# rev1.net
KiCad netlist of a schematic drawn in EAGLE
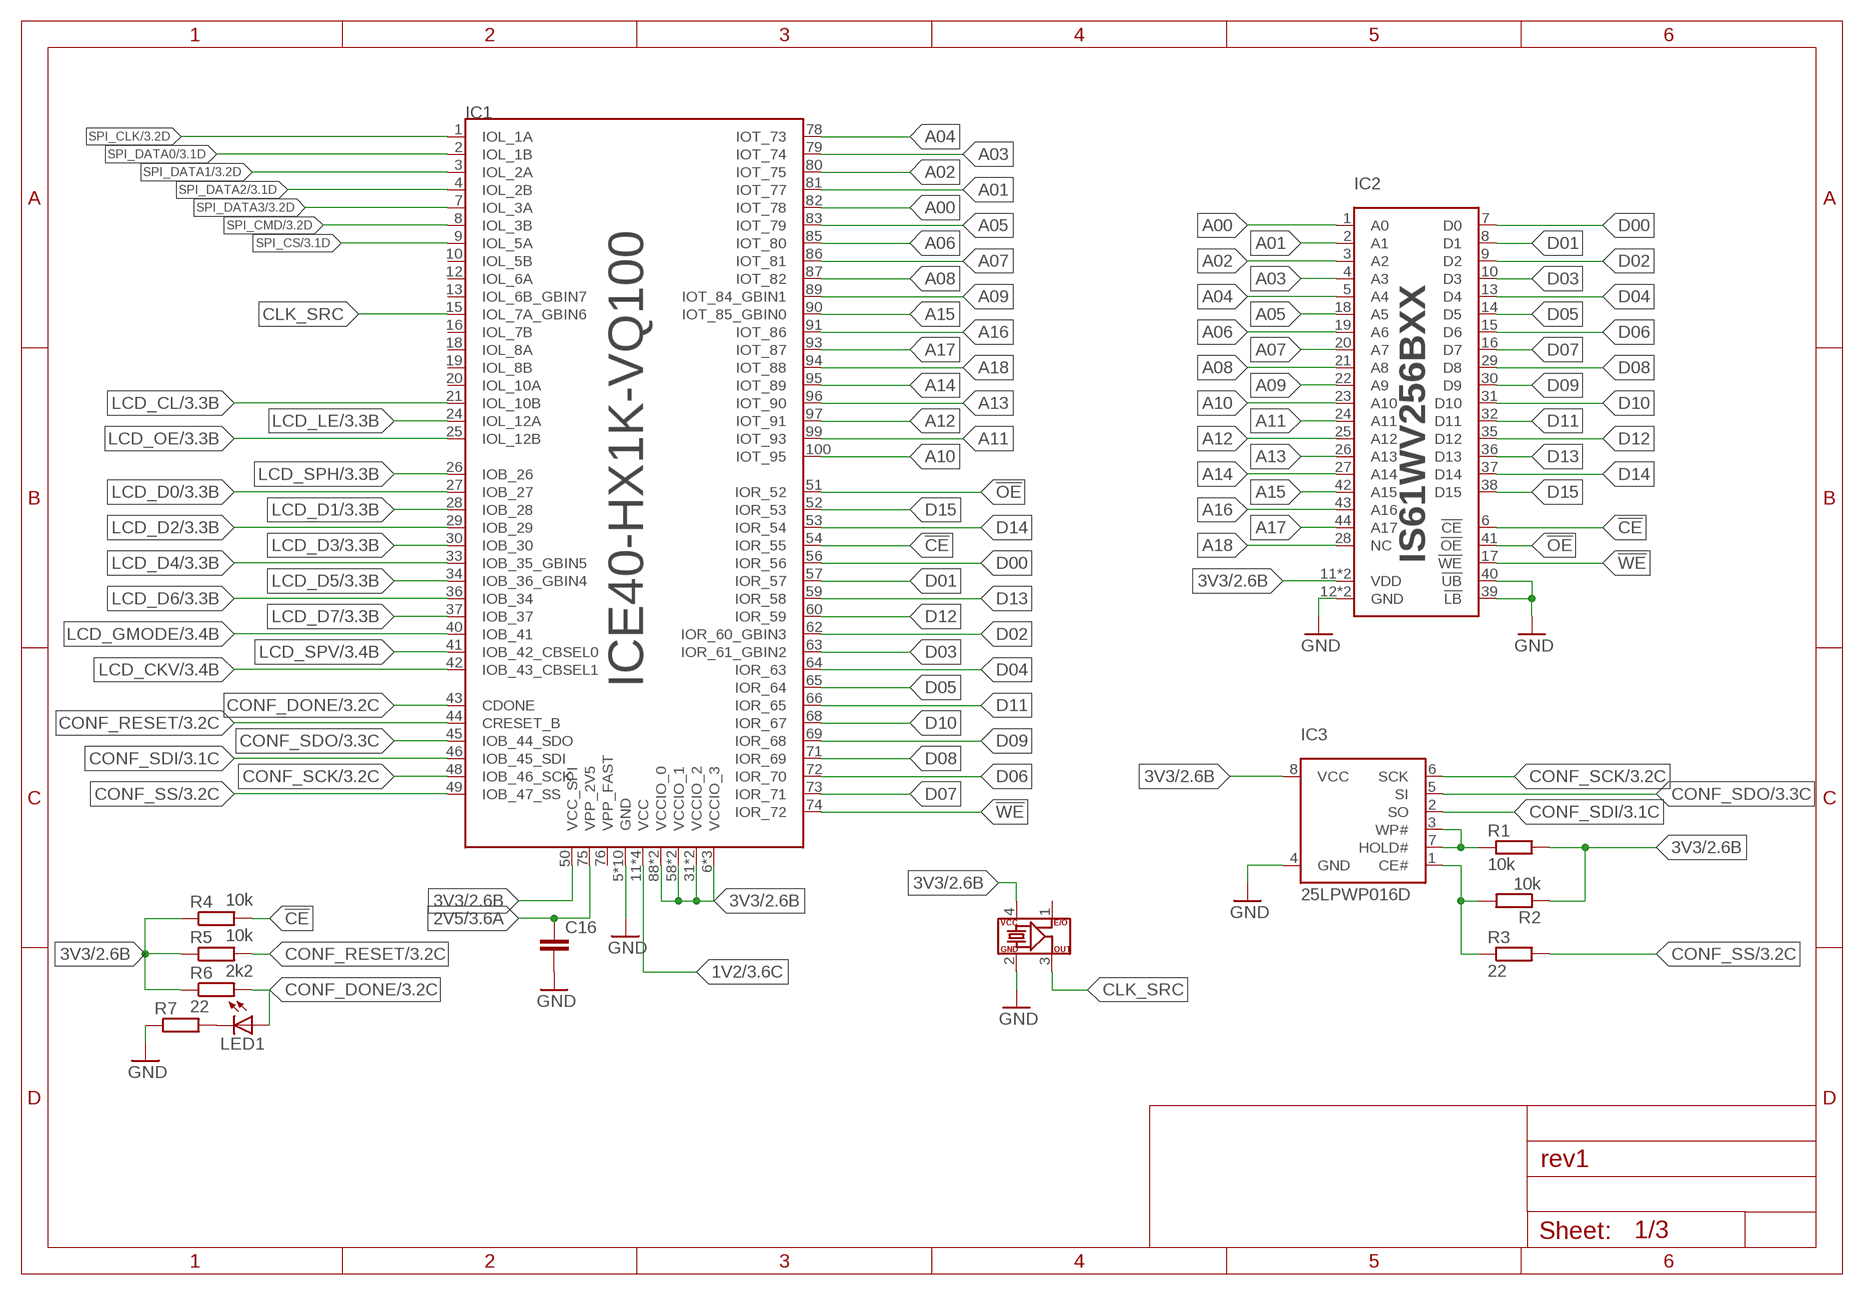
[diagram p0: schematic, sheet 1]
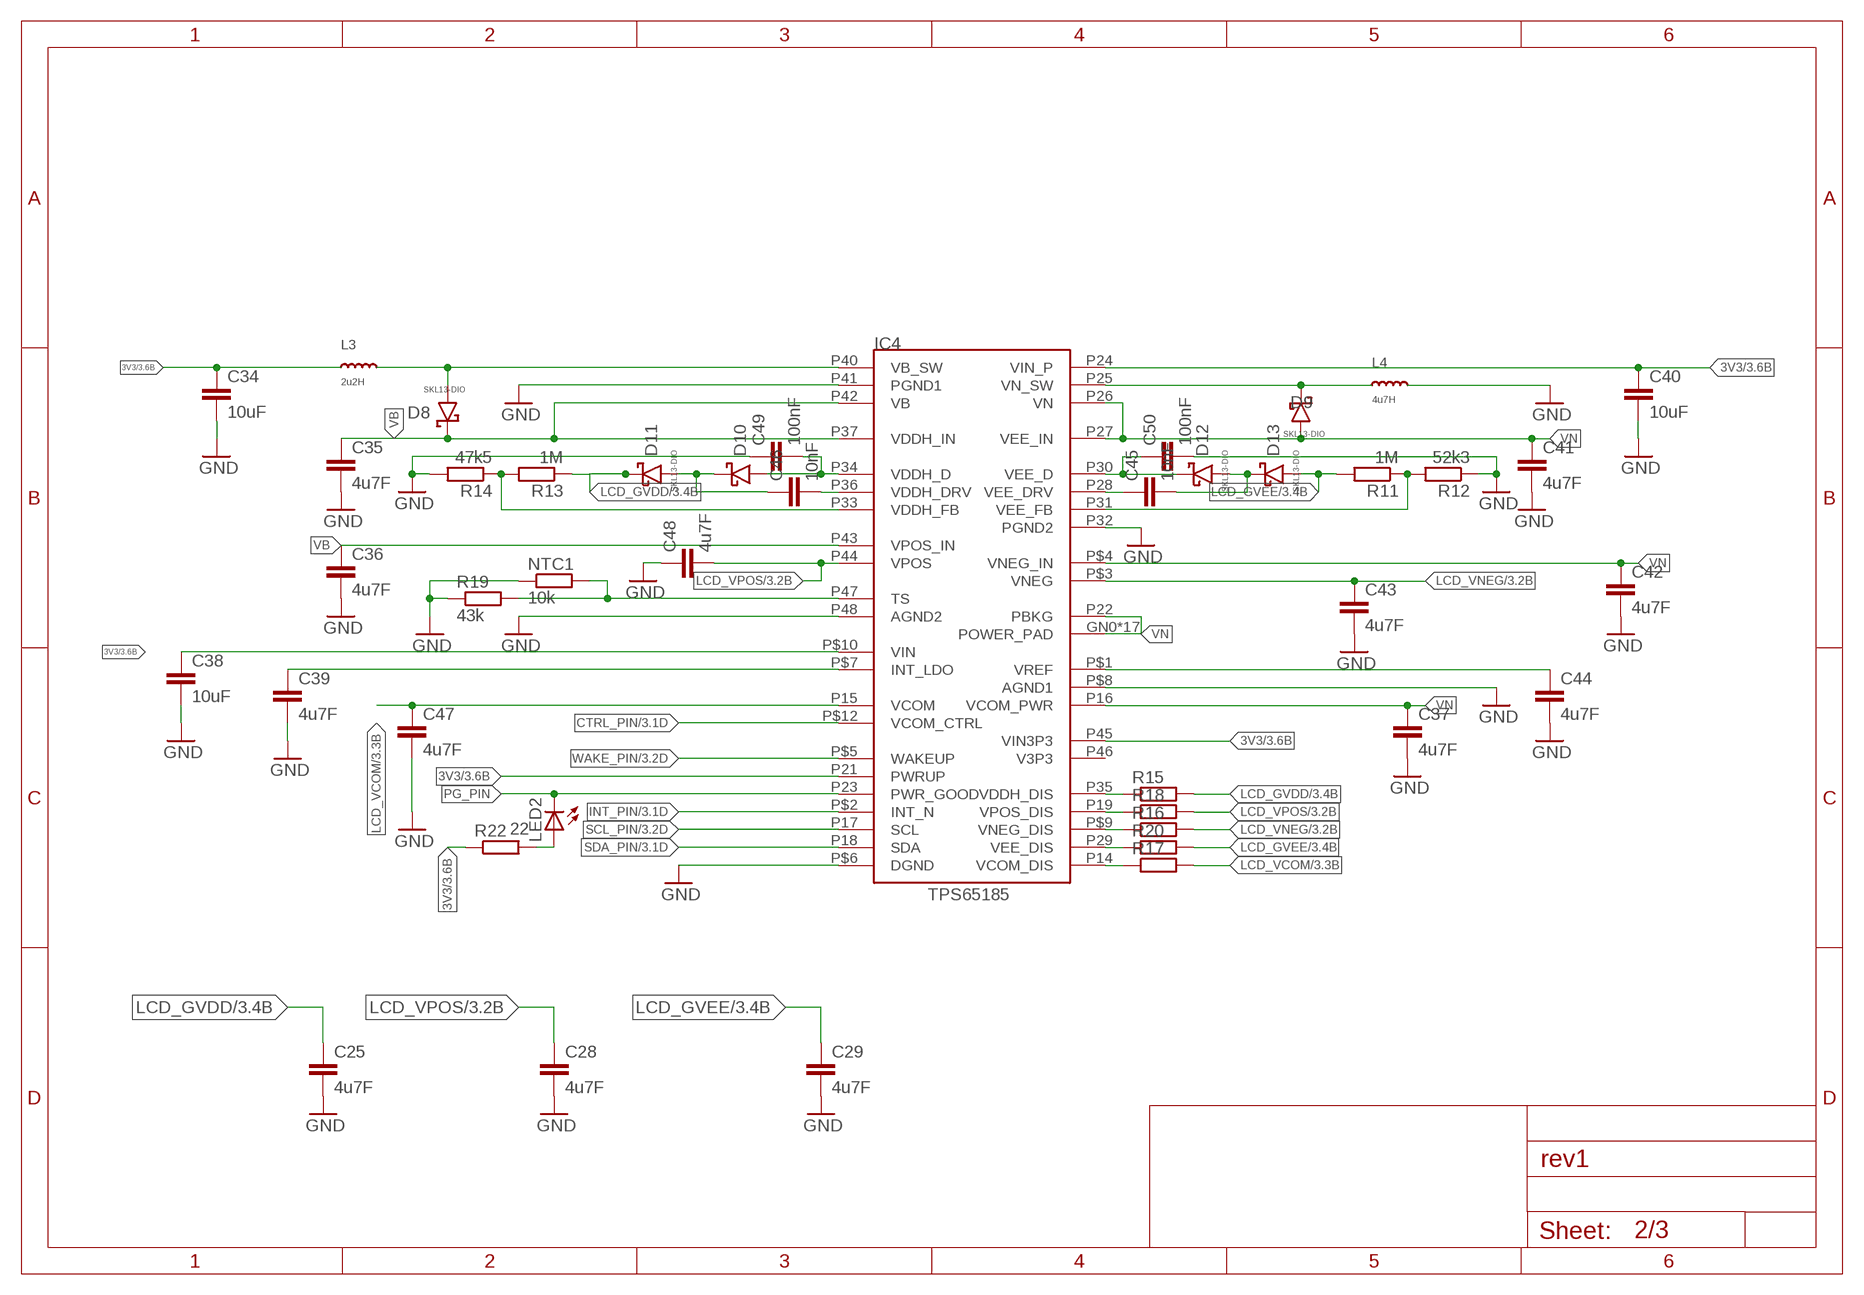
[diagram p1: schematic, sheet 2]
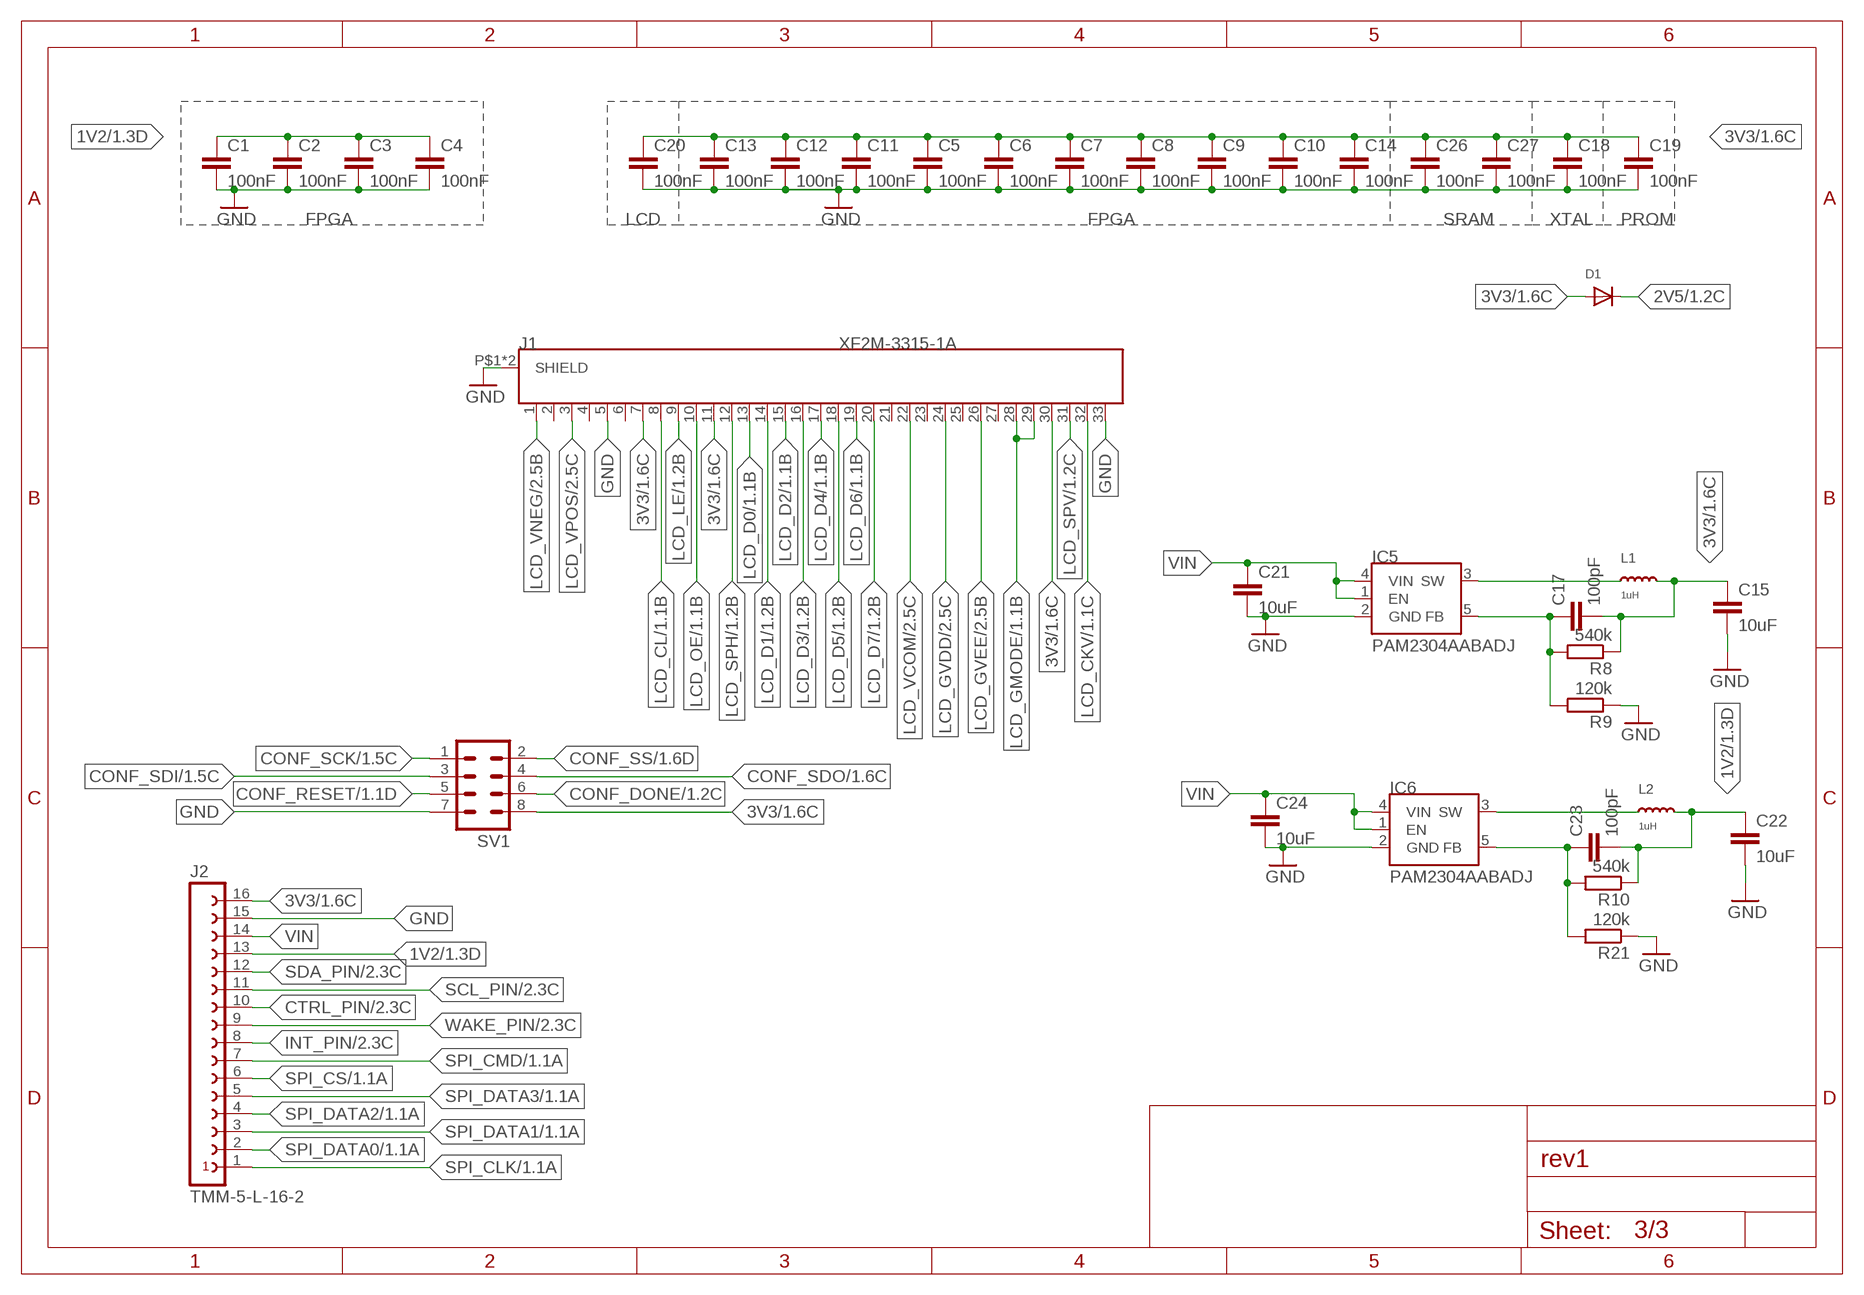
[diagram p2: schematic, sheet 3]

(export (version "E")
  (design (tool "Eeschema 10.0.6"))
  (components
    (comp (ref "C25")
      (value "4u7F")
      (footprint "eagle-import:C0805")
      (libsource (lib "eagle-import") (part "C-EUC0805"))
    )
    (comp (ref "C28")
      (value "4u7F")
      (footprint "eagle-import:C0805")
      (libsource (lib "eagle-import") (part "C-EUC0805"))
    )
    (comp (ref "C29")
      (value "4u7F")
      (footprint "eagle-import:C0805")
      (libsource (lib "eagle-import") (part "C-EUC0805"))
    )
    (comp (ref "C34")
      (value "10uF")
      (footprint "eagle-import:C0805")
      (libsource (lib "eagle-import") (part "C-EUC0805"))
    )
    (comp (ref "C35")
      (value "4u7F")
      (footprint "eagle-import:C0805")
      (libsource (lib "eagle-import") (part "C-EUC0805"))
    )
    (comp (ref "C36")
      (value "4u7F")
      (footprint "eagle-import:C0805")
      (libsource (lib "eagle-import") (part "C-EUC0805"))
    )
    (comp (ref "C37")
      (value "4u7F")
      (footprint "eagle-import:C0805")
      (libsource (lib "eagle-import") (part "C-EUC0805"))
    )
    (comp (ref "C38")
      (value "10uF")
      (footprint "eagle-import:C0805")
      (libsource (lib "eagle-import") (part "C-EUC0805"))
    )
    (comp (ref "C39")
      (value "4u7F")
      (footprint "eagle-import:C0603")
      (libsource (lib "eagle-import") (part "C-EUC0603"))
    )
    (comp (ref "C40")
      (value "10uF")
      (footprint "eagle-import:C0805")
      (libsource (lib "eagle-import") (part "C-EUC0805"))
    )
    (comp (ref "C41")
      (value "4u7F")
      (footprint "eagle-import:C0805")
      (libsource (lib "eagle-import") (part "C-EUC0805"))
    )
    (comp (ref "C42")
      (value "4u7F")
      (footprint "eagle-import:C0805")
      (libsource (lib "eagle-import") (part "C-EUC0805"))
    )
    (comp (ref "C43")
      (value "4u7F")
      (footprint "eagle-import:C0805")
      (libsource (lib "eagle-import") (part "C-EUC0805"))
    )
    (comp (ref "C44")
      (value "4u7F")
      (footprint "eagle-import:C0603")
      (libsource (lib "eagle-import") (part "C-EUC0603"))
    )
    (comp (ref "C45")
      (value "10nF")
      (footprint "eagle-import:C0402")
      (libsource (lib "eagle-import") (part "C-EUC0402"))
    )
    (comp (ref "C46")
      (value "10nF")
      (footprint "eagle-import:C0402")
      (libsource (lib "eagle-import") (part "C-EUC0402"))
    )
    (comp (ref "C47")
      (value "4u7F")
      (footprint "eagle-import:C0603")
      (libsource (lib "eagle-import") (part "C-EUC0603"))
    )
    (comp (ref "C48")
      (value "4u7F")
      (footprint "eagle-import:C0805")
      (libsource (lib "eagle-import") (part "C-EUC0805"))
    )
    (comp (ref "C49")
      (value "100nF")
      (footprint "eagle-import:C0402")
      (libsource (lib "eagle-import") (part "C-EUC0402"))
    )
    (comp (ref "C50")
      (value "100nF")
      (footprint "eagle-import:C0402")
      (libsource (lib "eagle-import") (part "C-EUC0402"))
    )
    (comp (ref "D8")
      (value "SKL13-DIO")
      (footprint "eagle-import:SOD523")
      (libsource (lib "eagle-import") (part "RB520S30T"))
    )
    (comp (ref "D9")
      (value "SKL13-DIO")
      (footprint "eagle-import:SOD523")
      (libsource (lib "eagle-import") (part "RB520S30T"))
    )
    (comp (ref "D10")
      (value "SKL13-DIO")
      (footprint "eagle-import:SOD523")
      (libsource (lib "eagle-import") (part "RB520S30T"))
    )
    (comp (ref "D11")
      (value "SKL13-DIO")
      (footprint "eagle-import:SOD523")
      (libsource (lib "eagle-import") (part "RB520S30T"))
    )
    (comp (ref "D12")
      (value "SKL13-DIO")
      (footprint "eagle-import:SOD523")
      (libsource (lib "eagle-import") (part "RB520S30T"))
    )
    (comp (ref "D13")
      (value "SKL13-DIO")
      (footprint "eagle-import:SOD523")
      (libsource (lib "eagle-import") (part "RB520S30T"))
    )
    (comp (ref "IC4")
      (value "TPS65185")
      (footprint "eagle-import:RGZ")
      (libsource (lib "eagle-import") (part "TPS65185"))
    )
    (comp (ref "L3")
      (value "2u2H")
      (footprint "eagle-import:3015")
      (libsource (lib "eagle-import") (part "DJNR-3015-2R2"))
    )
    (comp (ref "L4")
      (value "4u7H")
      (footprint "eagle-import:3015")
      (libsource (lib "eagle-import") (part "DJNR-3015-1R0"))
    )
    (comp (ref "LED2")
      (value "LEDCHIP-LED0603")
      (footprint "eagle-import:CHIP-LED0603")
      (libsource (lib "eagle-import") (part "LEDCHIP-LED0603"))
    )
    (comp (ref "NTC1")
      (value "10k")
      (footprint "eagle-import:R0603")
      (libsource (lib "eagle-import") (part "R-EU_R0603"))
    )
    (comp (ref "R11")
      (value "1M")
      (footprint "eagle-import:R0603")
      (libsource (lib "eagle-import") (part "R-EU_R0603"))
    )
    (comp (ref "R12")
      (value "52k3")
      (footprint "eagle-import:R0603")
      (libsource (lib "eagle-import") (part "R-EU_R0603"))
    )
    (comp (ref "R13")
      (value "1M")
      (footprint "eagle-import:R0603")
      (libsource (lib "eagle-import") (part "R-EU_R0603"))
    )
    (comp (ref "R14")
      (value "47k5")
      (footprint "eagle-import:R0603")
      (libsource (lib "eagle-import") (part "R-EU_R0603"))
    )
    (comp (ref "R15")
      (value "R-EU_R0603")
      (footprint "eagle-import:R0603")
      (libsource (lib "eagle-import") (part "R-EU_R0603"))
    )
    (comp (ref "R16")
      (value "R-EU_R0603")
      (footprint "eagle-import:R0603")
      (libsource (lib "eagle-import") (part "R-EU_R0603"))
    )
    (comp (ref "R17")
      (value "R-EU_R0603")
      (footprint "eagle-import:R0603")
      (libsource (lib "eagle-import") (part "R-EU_R0603"))
    )
    (comp (ref "R18")
      (value "R-EU_R0603")
      (footprint "eagle-import:R0603")
      (libsource (lib "eagle-import") (part "R-EU_R0603"))
    )
    (comp (ref "R19")
      (value "43k")
      (footprint "eagle-import:R0603")
      (libsource (lib "eagle-import") (part "R-EU_R0603"))
    )
    (comp (ref "R20")
      (value "R-EU_R0603")
      (footprint "eagle-import:R0603")
      (libsource (lib "eagle-import") (part "R-EU_R0603"))
    )
    (comp (ref "R22")
      (value "22")
      (footprint "eagle-import:R0402")
      (libsource (lib "eagle-import") (part "R-EU_R0402"))
    )
    (comp (ref "C16")
      (value "C-EUC0402")
      (footprint "eagle-import:C0402")
      (libsource (lib "eagle-import") (part "C-EUC0402"))
    )
    (comp (ref "IC1")
      (value "ICE40-HX1K-VQ100")
      (footprint "eagle-import:VQ100")
      (libsource (lib "eagle-import") (part "ICE40-HX1K-VQ100"))
    )
    (comp (ref "IC2")
      (value "IS61WV256BXX")
      (footprint "eagle-import:TSOP-2")
      (libsource (lib "eagle-import") (part "IS61WV256BXX"))
    )
    (comp (ref "IC3")
      (value "25LPWP016D")
      (footprint "eagle-import:SOP08")
      (libsource (lib "eagle-import") (part "25LPWP016D"))
    )
    (comp (ref "LED1")
      (value "LEDCHIP-LED0603")
      (footprint "eagle-import:CHIP-LED0603")
      (libsource (lib "eagle-import") (part "LEDCHIP-LED0603"))
    )
    (comp (ref "R1")
      (value "10k")
      (footprint "eagle-import:R0402")
      (libsource (lib "eagle-import") (part "R-EU_R0402"))
    )
    (comp (ref "R2")
      (value "10k")
      (footprint "eagle-import:R0603")
      (libsource (lib "eagle-import") (part "R-EU_R0603"))
    )
    (comp (ref "R3")
      (value "22")
      (footprint "eagle-import:R0402")
      (libsource (lib "eagle-import") (part "R-EU_R0402"))
    )
    (comp (ref "R4")
      (value "10k")
      (footprint "eagle-import:R0402")
      (libsource (lib "eagle-import") (part "R-EU_R0402"))
    )
    (comp (ref "R5")
      (value "10k")
      (footprint "eagle-import:R0402")
      (libsource (lib "eagle-import") (part "R-EU_R0402"))
    )
    (comp (ref "R6")
      (value "2k2")
      (footprint "eagle-import:R0402")
      (libsource (lib "eagle-import") (part "R-EU_R0402"))
    )
    (comp (ref "R7")
      (value "22")
      (footprint "eagle-import:R0402")
      (libsource (lib "eagle-import") (part "R-EU_R0402"))
    )
    (comp (ref "X1")
      (value "DSC61XX")
      (footprint "eagle-import:3225")
      (libsource (lib "eagle-import") (part "DSC61XX"))
    )
    (comp (ref "C1")
      (value "100nF")
      (footprint "eagle-import:C0402")
      (libsource (lib "eagle-import") (part "C-EUC0402"))
    )
    (comp (ref "C2")
      (value "100nF")
      (footprint "eagle-import:C0402")
      (libsource (lib "eagle-import") (part "C-EUC0402"))
    )
    (comp (ref "C3")
      (value "100nF")
      (footprint "eagle-import:C0402")
      (libsource (lib "eagle-import") (part "C-EUC0402"))
    )
    (comp (ref "C4")
      (value "100nF")
      (footprint "eagle-import:C0402")
      (libsource (lib "eagle-import") (part "C-EUC0402"))
    )
    (comp (ref "C5")
      (value "100nF")
      (footprint "eagle-import:C0402")
      (libsource (lib "eagle-import") (part "C-EUC0402"))
    )
    (comp (ref "C6")
      (value "100nF")
      (footprint "eagle-import:C0402")
      (libsource (lib "eagle-import") (part "C-EUC0402"))
    )
    (comp (ref "C7")
      (value "100nF")
      (footprint "eagle-import:C0402")
      (libsource (lib "eagle-import") (part "C-EUC0402"))
    )
    (comp (ref "C8")
      (value "100nF")
      (footprint "eagle-import:C0402")
      (libsource (lib "eagle-import") (part "C-EUC0402"))
    )
    (comp (ref "C9")
      (value "100nF")
      (footprint "eagle-import:C0402")
      (libsource (lib "eagle-import") (part "C-EUC0402"))
    )
    (comp (ref "C10")
      (value "100nF")
      (footprint "eagle-import:C0402")
      (libsource (lib "eagle-import") (part "C-EUC0402"))
    )
    (comp (ref "C11")
      (value "100nF")
      (footprint "eagle-import:C0402")
      (libsource (lib "eagle-import") (part "C-EUC0402"))
    )
    (comp (ref "C12")
      (value "100nF")
      (footprint "eagle-import:C0402")
      (libsource (lib "eagle-import") (part "C-EUC0402"))
    )
    (comp (ref "C13")
      (value "100nF")
      (footprint "eagle-import:C0402")
      (libsource (lib "eagle-import") (part "C-EUC0402"))
    )
    (comp (ref "C14")
      (value "100nF")
      (footprint "eagle-import:C0402")
      (libsource (lib "eagle-import") (part "C-EUC0402"))
    )
    (comp (ref "C15")
      (value "10uF")
      (footprint "eagle-import:C0603")
      (libsource (lib "eagle-import") (part "C-EUC0603"))
    )
    (comp (ref "C17")
      (value "100pF")
      (footprint "eagle-import:C0402")
      (libsource (lib "eagle-import") (part "C-EUC0402"))
    )
    (comp (ref "C18")
      (value "100nF")
      (footprint "eagle-import:C0402")
      (libsource (lib "eagle-import") (part "C-EUC0402"))
    )
    (comp (ref "C19")
      (value "100nF")
      (footprint "eagle-import:C0402")
      (libsource (lib "eagle-import") (part "C-EUC0402"))
    )
    (comp (ref "C20")
      (value "100nF")
      (footprint "eagle-import:C0402")
      (libsource (lib "eagle-import") (part "C-EUC0402"))
    )
    (comp (ref "C21")
      (value "10uF")
      (footprint "eagle-import:C0603")
      (libsource (lib "eagle-import") (part "C-EUC0603"))
    )
    (comp (ref "C22")
      (value "10uF")
      (footprint "eagle-import:C0603")
      (libsource (lib "eagle-import") (part "C-EUC0603"))
    )
    (comp (ref "C23")
      (value "100pF")
      (footprint "eagle-import:C0402")
      (libsource (lib "eagle-import") (part "C-EUC0402"))
    )
    (comp (ref "C24")
      (value "10uF")
      (footprint "eagle-import:C0603")
      (libsource (lib "eagle-import") (part "C-EUC0603"))
    )
    (comp (ref "C26")
      (value "100nF")
      (footprint "eagle-import:C0402")
      (libsource (lib "eagle-import") (part "C-EUC0402"))
    )
    (comp (ref "C27")
      (value "100nF")
      (footprint "eagle-import:C0402")
      (libsource (lib "eagle-import") (part "C-EUC0402"))
    )
    (comp (ref "D1")
      (value "DIODESOD-123")
      (footprint "eagle-import:SOD-123")
      (libsource (lib "eagle-import") (part "DIODESOD-123"))
    )
    (comp (ref "IC5")
      (value "PAM2304AABADJ")
      (footprint "eagle-import:TSOT25")
      (libsource (lib "eagle-import") (part "PAM2304AABADJ"))
    )
    (comp (ref "IC6")
      (value "PAM2304AABADJ")
      (footprint "eagle-import:TSOT25")
      (libsource (lib "eagle-import") (part "PAM2304AABADJ"))
    )
    (comp (ref "J1")
      (value "XF2M-3315-1A")
      (footprint "eagle-import:XF2M-3315-1A")
      (libsource (lib "eagle-import") (part "XF2M-3315-1A"))
    )
    (comp (ref "J2")
      (value "TMM-5-L-16-2")
      (footprint "eagle-import:TMM-5-L-16-2")
      (libsource (lib "eagle-import") (part "TMM-5-L-16-2"))
    )
    (comp (ref "L1")
      (value "1uH")
      (footprint "eagle-import:3015")
      (libsource (lib "eagle-import") (part "DJNR-3015-1R0"))
    )
    (comp (ref "L2")
      (value "1uH")
      (footprint "eagle-import:3015")
      (libsource (lib "eagle-import") (part "DJNR-3015-1R0"))
    )
    (comp (ref "R8")
      (value "540k")
      (footprint "eagle-import:R0402")
      (libsource (lib "eagle-import") (part "R-EU_R0402"))
    )
    (comp (ref "R9")
      (value "120k")
      (footprint "eagle-import:R0402")
      (libsource (lib "eagle-import") (part "R-EU_R0402"))
    )
    (comp (ref "R10")
      (value "540k")
      (footprint "eagle-import:R0402")
      (libsource (lib "eagle-import") (part "R-EU_R0402"))
    )
    (comp (ref "R21")
      (value "120k")
      (footprint "eagle-import:R0402")
      (libsource (lib "eagle-import") (part "R-EU_R0402"))
    )
    (comp (ref "SV1")
      (value "MA04-2")
      (footprint "eagle-import:MA04-2")
      (libsource (lib "eagle-import") (part "MA04-2"))
    )
  )
  (nets
    (net (code "1") (name "1V2") (class "Default")
      (node (ref "C1") (pin "1") (pinfunction "1_1") (pintype "passive"))
      (node (ref "C2") (pin "1") (pinfunction "1_1") (pintype "passive"))
      (node (ref "C22") (pin "1") (pinfunction "1_1") (pintype "passive"))
      (node (ref "C23") (pin "2") (pinfunction "2_2") (pintype "passive"))
      (node (ref "C3") (pin "1") (pinfunction "1_1") (pintype "passive"))
      (node (ref "C4") (pin "1") (pinfunction "1_1") (pintype "passive"))
      (node (ref "IC1") (pin "11") (pinfunction "VCC_11") (pintype "bidirectional"))
      (node (ref "IC1") (pin "35") (pinfunction "VCC_35") (pintype "bidirectional"))
      (node (ref "IC1") (pin "61") (pinfunction "VCC_61") (pintype "bidirectional"))
      (node (ref "IC1") (pin "77") (pinfunction "VCC_77") (pintype "bidirectional"))
      (node (ref "J2") (pin "13") (pinfunction "13_13") (pintype "passive"))
      (node (ref "L2") (pin "P$2") (pinfunction "P$2_P$2") (pintype "bidirectional"))
      (node (ref "R10") (pin "1") (pinfunction "1_1") (pintype "passive"))
    )
    (net (code "2") (name "2V5") (class "Default")
      (node (ref "C16") (pin "1") (pinfunction "1_1") (pintype "passive"))
      (node (ref "D1") (pin "C") (pinfunction "C_C") (pintype "passive"))
      (node (ref "IC1") (pin "75") (pinfunction "VPP_2V5_75") (pintype "bidirectional"))
    )
    (net (code "3") (name "3V3") (class "Default")
      (node (ref "C10") (pin "1") (pinfunction "1_1") (pintype "passive"))
      (node (ref "C11") (pin "1") (pinfunction "1_1") (pintype "passive"))
      (node (ref "C12") (pin "1") (pinfunction "1_1") (pintype "passive"))
      (node (ref "C13") (pin "1") (pinfunction "1_1") (pintype "passive"))
      (node (ref "C14") (pin "1") (pinfunction "1_1") (pintype "passive"))
      (node (ref "C15") (pin "1") (pinfunction "1_1") (pintype "passive"))
      (node (ref "C17") (pin "2") (pinfunction "2_2") (pintype "passive"))
      (node (ref "C18") (pin "1") (pinfunction "1_1") (pintype "passive"))
      (node (ref "C19") (pin "1") (pinfunction "1_1") (pintype "passive"))
      (node (ref "C20") (pin "1") (pinfunction "1_1") (pintype "passive"))
      (node (ref "C26") (pin "1") (pinfunction "1_1") (pintype "passive"))
      (node (ref "C27") (pin "1") (pinfunction "1_1") (pintype "passive"))
      (node (ref "C34") (pin "1") (pinfunction "1_1") (pintype "passive"))
      (node (ref "C38") (pin "1") (pinfunction "1_1") (pintype "passive"))
      (node (ref "C40") (pin "1") (pinfunction "1_1") (pintype "passive"))
      (node (ref "C5") (pin "1") (pinfunction "1_1") (pintype "passive"))
      (node (ref "C6") (pin "1") (pinfunction "1_1") (pintype "passive"))
      (node (ref "C7") (pin "1") (pinfunction "1_1") (pintype "passive"))
      (node (ref "C8") (pin "1") (pinfunction "1_1") (pintype "passive"))
      (node (ref "C9") (pin "1") (pinfunction "1_1") (pintype "passive"))
      (node (ref "D1") (pin "A") (pinfunction "A_A") (pintype "passive"))
      (node (ref "IC1") (pin "14") (pinfunction "VCCIO_3_14") (pintype "bidirectional"))
      (node (ref "IC1") (pin "22") (pinfunction "VCCIO_3_22") (pintype "bidirectional"))
      (node (ref "IC1") (pin "31") (pinfunction "VCCIO_2_31") (pintype "bidirectional"))
      (node (ref "IC1") (pin "38") (pinfunction "VCCIO_2_38") (pintype "bidirectional"))
      (node (ref "IC1") (pin "50") (pinfunction "VCC_SPI_50") (pintype "bidirectional"))
      (node (ref "IC1") (pin "58") (pinfunction "VCCIO_1_58") (pintype "bidirectional"))
      (node (ref "IC1") (pin "6") (pinfunction "VCCIO_3_6") (pintype "bidirectional"))
      (node (ref "IC1") (pin "67") (pinfunction "VCCIO_1_67") (pintype "bidirectional"))
      (node (ref "IC1") (pin "88") (pinfunction "VCCIO_0_88") (pintype "bidirectional"))
      (node (ref "IC1") (pin "92") (pinfunction "VCCIO_0_92") (pintype "bidirectional"))
      (node (ref "IC2") (pin "11") (pinfunction "VDD_11") (pintype "bidirectional"))
      (node (ref "IC2") (pin "33") (pinfunction "VDD_33") (pintype "bidirectional"))
      (node (ref "IC3") (pin "8") (pinfunction "VCC_8") (pintype "bidirectional"))
      (node (ref "IC4") (pin "P$10") (pinfunction "VIN_P$10") (pintype "bidirectional"))
      (node (ref "IC4") (pin "P21") (pinfunction "PWRUP_P21") (pintype "bidirectional"))
      (node (ref "IC4") (pin "P24") (pinfunction "VIN_P_P24") (pintype "bidirectional"))
      (node (ref "IC4") (pin "P45") (pinfunction "VIN3P3_P45") (pintype "bidirectional"))
      (node (ref "J1") (pin "11") (pinfunction "P$11_11") (pintype "bidirectional"))
      (node (ref "J1") (pin "30") (pinfunction "P$30_30") (pintype "bidirectional"))
      (node (ref "J1") (pin "7") (pinfunction "P$7_7") (pintype "bidirectional"))
      (node (ref "J2") (pin "16") (pinfunction "16_16") (pintype "passive"))
      (node (ref "L1") (pin "P$2") (pinfunction "P$2_P$2") (pintype "bidirectional"))
      (node (ref "L3") (pin "P$1") (pinfunction "P$1_P$1") (pintype "bidirectional"))
      (node (ref "R1") (pin "2") (pinfunction "2_2") (pintype "passive"))
      (node (ref "R2") (pin "1") (pinfunction "1_1") (pintype "passive"))
      (node (ref "R22") (pin "1") (pinfunction "1_1") (pintype "passive"))
      (node (ref "R4") (pin "1") (pinfunction "1_1") (pintype "passive"))
      (node (ref "R5") (pin "1") (pinfunction "1_1") (pintype "passive"))
      (node (ref "R6") (pin "1") (pinfunction "1_1") (pintype "passive"))
      (node (ref "R8") (pin "1") (pinfunction "1_1") (pintype "passive"))
      (node (ref "SV1") (pin "8") (pinfunction "8_8") (pintype "passive"))
      (node (ref "X1") (pin "4") (pinfunction "4_4") (pintype "bidirectional"))
    )
    (net (code "4") (name "A00") (class "Default")
      (node (ref "IC1") (pin "82") (pinfunction "IOT_78_82") (pintype "bidirectional"))
      (node (ref "IC2") (pin "1") (pinfunction "A0_1") (pintype "bidirectional"))
    )
    (net (code "5") (name "A01") (class "Default")
      (node (ref "IC1") (pin "81") (pinfunction "IOT_77_81") (pintype "bidirectional"))
      (node (ref "IC2") (pin "2") (pinfunction "A1_2") (pintype "bidirectional"))
    )
    (net (code "6") (name "A02") (class "Default")
      (node (ref "IC1") (pin "80") (pinfunction "IOT_75_80") (pintype "bidirectional"))
      (node (ref "IC2") (pin "3") (pinfunction "A2_3") (pintype "bidirectional"))
    )
    (net (code "7") (name "A03") (class "Default")
      (node (ref "IC1") (pin "79") (pinfunction "IOT_74_79") (pintype "bidirectional"))
      (node (ref "IC2") (pin "4") (pinfunction "A3_4") (pintype "bidirectional"))
    )
    (net (code "8") (name "A04") (class "Default")
      (node (ref "IC1") (pin "78") (pinfunction "IOT_73_78") (pintype "bidirectional"))
      (node (ref "IC2") (pin "5") (pinfunction "A4_5") (pintype "bidirectional"))
    )
    (net (code "9") (name "A05") (class "Default")
      (node (ref "IC1") (pin "83") (pinfunction "IOT_79_83") (pintype "bidirectional"))
      (node (ref "IC2") (pin "18") (pinfunction "A5_18") (pintype "bidirectional"))
    )
    (net (code "10") (name "A06") (class "Default")
      (node (ref "IC1") (pin "85") (pinfunction "IOT_80_85") (pintype "bidirectional"))
      (node (ref "IC2") (pin "19") (pinfunction "A6_19") (pintype "bidirectional"))
    )
    (net (code "11") (name "A07") (class "Default")
      (node (ref "IC1") (pin "86") (pinfunction "IOT_81_86") (pintype "bidirectional"))
      (node (ref "IC2") (pin "20") (pinfunction "A7_20") (pintype "bidirectional"))
    )
    (net (code "12") (name "A08") (class "Default")
      (node (ref "IC1") (pin "87") (pinfunction "IOT_82_87") (pintype "bidirectional"))
      (node (ref "IC2") (pin "21") (pinfunction "A8_21") (pintype "bidirectional"))
    )
    (net (code "13") (name "A09") (class "Default")
      (node (ref "IC1") (pin "89") (pinfunction "IOT_84_GBIN1_89") (pintype "bidirectional"))
      (node (ref "IC2") (pin "22") (pinfunction "A9_22") (pintype "bidirectional"))
    )
    (net (code "14") (name "A10") (class "Default")
      (node (ref "IC1") (pin "100") (pinfunction "IOT_95_100") (pintype "bidirectional"))
      (node (ref "IC2") (pin "23") (pinfunction "A10_23") (pintype "bidirectional"))
    )
    (net (code "15") (name "A11") (class "Default")
      (node (ref "IC1") (pin "99") (pinfunction "IOT_93_99") (pintype "bidirectional"))
      (node (ref "IC2") (pin "24") (pinfunction "A11_24") (pintype "bidirectional"))
    )
    (net (code "16") (name "A12") (class "Default")
      (node (ref "IC1") (pin "97") (pinfunction "IOT_91_97") (pintype "bidirectional"))
      (node (ref "IC2") (pin "25") (pinfunction "A12_25") (pintype "bidirectional"))
    )
    (net (code "17") (name "A13") (class "Default")
      (node (ref "IC1") (pin "96") (pinfunction "IOT_90_96") (pintype "bidirectional"))
      (node (ref "IC2") (pin "26") (pinfunction "A13_26") (pintype "bidirectional"))
    )
    (net (code "18") (name "A14") (class "Default")
      (node (ref "IC1") (pin "95") (pinfunction "IOT_89_95") (pintype "bidirectional"))
      (node (ref "IC2") (pin "27") (pinfunction "A14_27") (pintype "bidirectional"))
    )
    (net (code "19") (name "A15") (class "Default")
      (node (ref "IC1") (pin "90") (pinfunction "IOT_85_GBIN0_90") (pintype "bidirectional"))
      (node (ref "IC2") (pin "42") (pinfunction "A15_42") (pintype "bidirectional"))
    )
    (net (code "20") (name "A16") (class "Default")
      (node (ref "IC1") (pin "91") (pinfunction "IOT_86_91") (pintype "bidirectional"))
      (node (ref "IC2") (pin "43") (pinfunction "A16_43") (pintype "bidirectional"))
    )
    (net (code "21") (name "A17") (class "Default")
      (node (ref "IC1") (pin "93") (pinfunction "IOT_87_93") (pintype "bidirectional"))
      (node (ref "IC2") (pin "44") (pinfunction "A17_44") (pintype "bidirectional"))
    )
    (net (code "22") (name "A18") (class "Default")
      (node (ref "IC1") (pin "94") (pinfunction "IOT_88_94") (pintype "bidirectional"))
      (node (ref "IC2") (pin "28") (pinfunction "NC_28") (pintype "bidirectional"))
    )
    (net (code "23") (name "CLK_SRC") (class "Default")
      (node (ref "IC1") (pin "15") (pinfunction "IOL_7A_GBIN6_15") (pintype "bidirectional"))
      (node (ref "X1") (pin "3") (pinfunction "3_3") (pintype "bidirectional"))
    )
    (net (code "24") (name "CONF_DONE") (class "Default")
      (node (ref "IC1") (pin "43") (pinfunction "CDONE_43") (pintype "bidirectional"))
      (node (ref "LED1") (pin "A") (pinfunction "A_A") (pintype "passive"))
      (node (ref "R6") (pin "2") (pinfunction "2_2") (pintype "passive"))
      (node (ref "SV1") (pin "6") (pinfunction "6_6") (pintype "passive"))
    )
    (net (code "25") (name "CONF_RESET") (class "Default")
      (node (ref "IC1") (pin "44") (pinfunction "CRESET_B_44") (pintype "bidirectional"))
      (node (ref "R5") (pin "2") (pinfunction "2_2") (pintype "passive"))
      (node (ref "SV1") (pin "5") (pinfunction "5_5") (pintype "passive"))
    )
    (net (code "26") (name "CONF_SCK") (class "Default")
      (node (ref "IC1") (pin "48") (pinfunction "IOB_46_SCK_48") (pintype "bidirectional"))
      (node (ref "IC3") (pin "6") (pinfunction "SCK_6") (pintype "bidirectional"))
      (node (ref "SV1") (pin "1") (pinfunction "1_1") (pintype "passive"))
    )
    (net (code "27") (name "CONF_SDI") (class "Default")
      (node (ref "IC1") (pin "46") (pinfunction "IOB_45_SDI_46") (pintype "bidirectional"))
      (node (ref "IC3") (pin "2") (pinfunction "SO_2") (pintype "bidirectional"))
      (node (ref "SV1") (pin "3") (pinfunction "3_3") (pintype "passive"))
    )
    (net (code "28") (name "CONF_SDO") (class "Default")
      (node (ref "IC1") (pin "45") (pinfunction "IOB_44_SDO_45") (pintype "bidirectional"))
      (node (ref "IC3") (pin "5") (pinfunction "SI_5") (pintype "bidirectional"))
      (node (ref "SV1") (pin "4") (pinfunction "4_4") (pintype "passive"))
    )
    (net (code "29") (name "CONF_SS") (class "Default")
      (node (ref "IC1") (pin "49") (pinfunction "IOB_47_SS_49") (pintype "bidirectional"))
      (node (ref "R3") (pin "2") (pinfunction "2_2") (pintype "passive"))
      (node (ref "SV1") (pin "2") (pinfunction "2_2") (pintype "passive"))
    )
    (net (code "30") (name "CTRL_PIN") (class "Default")
      (node (ref "IC4") (pin "P$12") (pinfunction "VCOM_CTRL_P$12") (pintype "bidirectional"))
      (node (ref "J2") (pin "10") (pinfunction "10_10") (pintype "passive"))
    )
    (net (code "31") (name "D00") (class "Default")
      (node (ref "IC1") (pin "56") (pinfunction "IOR_56_56") (pintype "bidirectional"))
      (node (ref "IC2") (pin "7") (pinfunction "D0_7") (pintype "bidirectional"))
    )
    (net (code "32") (name "D01") (class "Default")
      (node (ref "IC1") (pin "57") (pinfunction "IOR_57_57") (pintype "bidirectional"))
      (node (ref "IC2") (pin "8") (pinfunction "D1_8") (pintype "bidirectional"))
    )
    (net (code "33") (name "D02") (class "Default")
      (node (ref "IC1") (pin "62") (pinfunction "IOR_60_GBIN3_62") (pintype "bidirectional"))
      (node (ref "IC2") (pin "9") (pinfunction "D2_9") (pintype "bidirectional"))
    )
    (net (code "34") (name "D03") (class "Default")
      (node (ref "IC1") (pin "63") (pinfunction "IOR_61_GBIN2_63") (pintype "bidirectional"))
      (node (ref "IC2") (pin "10") (pinfunction "D3_10") (pintype "bidirectional"))
    )
    (net (code "35") (name "D04") (class "Default")
      (node (ref "IC1") (pin "64") (pinfunction "IOR_63_64") (pintype "bidirectional"))
      (node (ref "IC2") (pin "13") (pinfunction "D4_13") (pintype "bidirectional"))
    )
    (net (code "36") (name "D05") (class "Default")
      (node (ref "IC1") (pin "65") (pinfunction "IOR_64_65") (pintype "bidirectional"))
      (node (ref "IC2") (pin "14") (pinfunction "D5_14") (pintype "bidirectional"))
    )
    (net (code "37") (name "D06") (class "Default")
      (node (ref "IC1") (pin "72") (pinfunction "IOR_70_72") (pintype "bidirectional"))
      (node (ref "IC2") (pin "15") (pinfunction "D6_15") (pintype "bidirectional"))
    )
    (net (code "38") (name "D07") (class "Default")
      (node (ref "IC1") (pin "73") (pinfunction "IOR_71_73") (pintype "bidirectional"))
      (node (ref "IC2") (pin "16") (pinfunction "D7_16") (pintype "bidirectional"))
    )
    (net (code "39") (name "D08") (class "Default")
      (node (ref "IC1") (pin "71") (pinfunction "IOR_69_71") (pintype "bidirectional"))
      (node (ref "IC2") (pin "29") (pinfunction "D8_29") (pintype "bidirectional"))
    )
    (net (code "40") (name "D09") (class "Default")
      (node (ref "IC1") (pin "69") (pinfunction "IOR_68_69") (pintype "bidirectional"))
      (node (ref "IC2") (pin "30") (pinfunction "D9_30") (pintype "bidirectional"))
    )
    (net (code "41") (name "D10") (class "Default")
      (node (ref "IC1") (pin "68") (pinfunction "IOR_67_68") (pintype "bidirectional"))
      (node (ref "IC2") (pin "31") (pinfunction "D10_31") (pintype "bidirectional"))
    )
    (net (code "42") (name "D11") (class "Default")
      (node (ref "IC1") (pin "66") (pinfunction "IOR_65_66") (pintype "bidirectional"))
      (node (ref "IC2") (pin "32") (pinfunction "D11_32") (pintype "bidirectional"))
    )
    (net (code "43") (name "D12") (class "Default")
      (node (ref "IC1") (pin "60") (pinfunction "IOR_59_60") (pintype "bidirectional"))
      (node (ref "IC2") (pin "35") (pinfunction "D12_35") (pintype "bidirectional"))
    )
    (net (code "44") (name "D13") (class "Default")
      (node (ref "IC1") (pin "59") (pinfunction "IOR_58_59") (pintype "bidirectional"))
      (node (ref "IC2") (pin "36") (pinfunction "D13_36") (pintype "bidirectional"))
    )
    (net (code "45") (name "D14") (class "Default")
      (node (ref "IC1") (pin "53") (pinfunction "IOR_54_53") (pintype "bidirectional"))
      (node (ref "IC2") (pin "37") (pinfunction "D14_37") (pintype "bidirectional"))
    )
    (net (code "46") (name "D15") (class "Default")
      (node (ref "IC1") (pin "52") (pinfunction "IOR_53_52") (pintype "bidirectional"))
      (node (ref "IC2") (pin "38") (pinfunction "D15_38") (pintype "bidirectional"))
    )
    (net (code "47") (name "GND") (class "Default")
      (node (ref "C1") (pin "2") (pinfunction "2_2") (pintype "passive"))
      (node (ref "C10") (pin "2") (pinfunction "2_2") (pintype "passive"))
      (node (ref "C11") (pin "2") (pinfunction "2_2") (pintype "passive"))
      (node (ref "C12") (pin "2") (pinfunction "2_2") (pintype "passive"))
      (node (ref "C13") (pin "2") (pinfunction "2_2") (pintype "passive"))
      (node (ref "C14") (pin "2") (pinfunction "2_2") (pintype "passive"))
      (node (ref "C15") (pin "2") (pinfunction "2_2") (pintype "passive"))
      (node (ref "C16") (pin "2") (pinfunction "2_2") (pintype "passive"))
      (node (ref "C18") (pin "2") (pinfunction "2_2") (pintype "passive"))
      (node (ref "C19") (pin "2") (pinfunction "2_2") (pintype "passive"))
      (node (ref "C2") (pin "2") (pinfunction "2_2") (pintype "passive"))
      (node (ref "C20") (pin "2") (pinfunction "2_2") (pintype "passive"))
      (node (ref "C21") (pin "2") (pinfunction "2_2") (pintype "passive"))
      (node (ref "C22") (pin "2") (pinfunction "2_2") (pintype "passive"))
      (node (ref "C24") (pin "2") (pinfunction "2_2") (pintype "passive"))
      (node (ref "C25") (pin "2") (pinfunction "2_2") (pintype "passive"))
      (node (ref "C26") (pin "2") (pinfunction "2_2") (pintype "passive"))
      (node (ref "C27") (pin "2") (pinfunction "2_2") (pintype "passive"))
      (node (ref "C28") (pin "2") (pinfunction "2_2") (pintype "passive"))
      (node (ref "C29") (pin "2") (pinfunction "2_2") (pintype "passive"))
      (node (ref "C3") (pin "2") (pinfunction "2_2") (pintype "passive"))
      (node (ref "C34") (pin "2") (pinfunction "2_2") (pintype "passive"))
      (node (ref "C35") (pin "2") (pinfunction "2_2") (pintype "passive"))
      (node (ref "C36") (pin "2") (pinfunction "2_2") (pintype "passive"))
      (node (ref "C37") (pin "2") (pinfunction "2_2") (pintype "passive"))
      (node (ref "C38") (pin "2") (pinfunction "2_2") (pintype "passive"))
      (node (ref "C39") (pin "2") (pinfunction "2_2") (pintype "passive"))
      (node (ref "C4") (pin "2") (pinfunction "2_2") (pintype "passive"))
      (node (ref "C40") (pin "2") (pinfunction "2_2") (pintype "passive"))
      (node (ref "C41") (pin "2") (pinfunction "2_2") (pintype "passive"))
      (node (ref "C42") (pin "2") (pinfunction "2_2") (pintype "passive"))
      (node (ref "C43") (pin "2") (pinfunction "2_2") (pintype "passive"))
      (node (ref "C44") (pin "2") (pinfunction "2_2") (pintype "passive"))
      (node (ref "C47") (pin "2") (pinfunction "2_2") (pintype "passive"))
      (node (ref "C48") (pin "1") (pinfunction "1_1") (pintype "passive"))
      (node (ref "C49") (pin "1") (pinfunction "1_1") (pintype "passive"))
      (node (ref "C5") (pin "2") (pinfunction "2_2") (pintype "passive"))
      (node (ref "C50") (pin "2") (pinfunction "2_2") (pintype "passive"))
      (node (ref "C6") (pin "2") (pinfunction "2_2") (pintype "passive"))
      (node (ref "C7") (pin "2") (pinfunction "2_2") (pintype "passive"))
      (node (ref "C8") (pin "2") (pinfunction "2_2") (pintype "passive"))
      (node (ref "C9") (pin "2") (pinfunction "2_2") (pintype "passive"))
      (node (ref "IC1") (pin "17") (pinfunction "GND_17") (pintype "bidirectional"))
      (node (ref "IC1") (pin "23") (pinfunction "GND_23") (pintype "bidirectional"))
      (node (ref "IC1") (pin "32") (pinfunction "GND_32") (pintype "bidirectional"))
      (node (ref "IC1") (pin "39") (pinfunction "GND_39") (pintype "bidirectional"))
      (node (ref "IC1") (pin "47") (pinfunction "GND_47") (pintype "bidirectional"))
      (node (ref "IC1") (pin "5") (pinfunction "GND_5") (pintype "bidirectional"))
      (node (ref "IC1") (pin "55") (pinfunction "GND_55") (pintype "bidirectional"))
      (node (ref "IC1") (pin "70") (pinfunction "GND_70") (pintype "bidirectional"))
      (node (ref "IC1") (pin "84") (pinfunction "GND_84") (pintype "bidirectional"))
      (node (ref "IC1") (pin "98") (pinfunction "GND_98") (pintype "bidirectional"))
      (node (ref "IC2") (pin "12") (pinfunction "GND_12") (pintype "bidirectional"))
      (node (ref "IC2") (pin "34") (pinfunction "GND_34") (pintype "bidirectional"))
      (node (ref "IC2") (pin "39") (pinfunction "~{LB}_39") (pintype "bidirectional"))
      (node (ref "IC2") (pin "40") (pinfunction "~{UB}_40") (pintype "bidirectional"))
      (node (ref "IC3") (pin "4") (pinfunction "GND_4") (pintype "bidirectional"))
      (node (ref "IC4") (pin "P$6") (pinfunction "DGND_P$6") (pintype "bidirectional"))
      (node (ref "IC4") (pin "P$8") (pinfunction "AGND1_P$8") (pintype "bidirectional"))
      (node (ref "IC4") (pin "P32") (pinfunction "PGND2_P32") (pintype "bidirectional"))
      (node (ref "IC4") (pin "P41") (pinfunction "PGND1_P41") (pintype "bidirectional"))
      (node (ref "IC4") (pin "P48") (pinfunction "AGND2_P48") (pintype "bidirectional"))
      (node (ref "IC5") (pin "2") (pinfunction "GND_2") (pintype "bidirectional"))
      (node (ref "IC6") (pin "2") (pinfunction "GND_2") (pintype "bidirectional"))
      (node (ref "J1") (pin "33") (pinfunction "P$33_33") (pintype "bidirectional"))
      (node (ref "J1") (pin "5") (pinfunction "P$5_5") (pintype "bidirectional"))
      (node (ref "J1") (pin "P$1") (pinfunction "SHIELD_P$1") (pintype "bidirectional"))
      (node (ref "J1") (pin "P$2") (pinfunction "SHIELD_P$2") (pintype "bidirectional"))
      (node (ref "J2") (pin "15") (pinfunction "15_15") (pintype "passive"))
      (node (ref "L4") (pin "P$2") (pinfunction "P$2_P$2") (pintype "bidirectional"))
      (node (ref "NTC1") (pin "1") (pinfunction "1_1") (pintype "passive"))
      (node (ref "R12") (pin "1") (pinfunction "1_1") (pintype "passive"))
      (node (ref "R14") (pin "2") (pinfunction "2_2") (pintype "passive"))
      (node (ref "R19") (pin "1") (pinfunction "1_1") (pintype "passive"))
      (node (ref "R21") (pin "1") (pinfunction "1_1") (pintype "passive"))
      (node (ref "R7") (pin "1") (pinfunction "1_1") (pintype "passive"))
      (node (ref "R9") (pin "1") (pinfunction "1_1") (pintype "passive"))
      (node (ref "SV1") (pin "7") (pinfunction "7_7") (pintype "passive"))
      (node (ref "X1") (pin "2") (pinfunction "2_2") (pintype "bidirectional"))
    )
    (net (code "48") (name "INT_PIN") (class "Default")
      (node (ref "IC4") (pin "P$2") (pinfunction "INT_N_P$2") (pintype "bidirectional"))
      (node (ref "J2") (pin "8") (pinfunction "8_8") (pintype "passive"))
    )
    (net (code "49") (name "LCD_CKV") (class "Default")
      (node (ref "IC1") (pin "42") (pinfunction "IOB_43_CBSEL1_42") (pintype "bidirectional"))
      (node (ref "J1") (pin "32") (pinfunction "P$32_32") (pintype "bidirectional"))
    )
    (net (code "50") (name "LCD_CL") (class "Default")
      (node (ref "IC1") (pin "21") (pinfunction "IOL_10B_21") (pintype "bidirectional"))
      (node (ref "J1") (pin "8") (pinfunction "P$8_8") (pintype "bidirectional"))
    )
    (net (code "51") (name "LCD_D0") (class "Default")
      (node (ref "IC1") (pin "27") (pinfunction "IOB_27_27") (pintype "bidirectional"))
      (node (ref "J1") (pin "13") (pinfunction "P$13_13") (pintype "bidirectional"))
    )
    (net (code "52") (name "LCD_D1") (class "Default")
      (node (ref "IC1") (pin "28") (pinfunction "IOB_28_28") (pintype "bidirectional"))
      (node (ref "J1") (pin "14") (pinfunction "P$14_14") (pintype "bidirectional"))
    )
    (net (code "53") (name "LCD_D2") (class "Default")
      (node (ref "IC1") (pin "29") (pinfunction "IOB_29_29") (pintype "bidirectional"))
      (node (ref "J1") (pin "15") (pinfunction "P$15_15") (pintype "bidirectional"))
    )
    (net (code "54") (name "LCD_D3") (class "Default")
      (node (ref "IC1") (pin "30") (pinfunction "IOB_30_30") (pintype "bidirectional"))
      (node (ref "J1") (pin "16") (pinfunction "P$16_16") (pintype "bidirectional"))
    )
    (net (code "55") (name "LCD_D4") (class "Default")
      (node (ref "IC1") (pin "33") (pinfunction "IOB_35_GBIN5_33") (pintype "bidirectional"))
      (node (ref "J1") (pin "17") (pinfunction "P$17_17") (pintype "bidirectional"))
    )
    (net (code "56") (name "LCD_D5") (class "Default")
      (node (ref "IC1") (pin "34") (pinfunction "IOB_36_GBIN4_34") (pintype "bidirectional"))
      (node (ref "J1") (pin "18") (pinfunction "P$18_18") (pintype "bidirectional"))
    )
    (net (code "57") (name "LCD_D6") (class "Default")
      (node (ref "IC1") (pin "36") (pinfunction "IOB_34_36") (pintype "bidirectional"))
      (node (ref "J1") (pin "19") (pinfunction "P$19_19") (pintype "bidirectional"))
    )
    (net (code "58") (name "LCD_D7") (class "Default")
      (node (ref "IC1") (pin "37") (pinfunction "IOB_37_37") (pintype "bidirectional"))
      (node (ref "J1") (pin "20") (pinfunction "P$20_20") (pintype "bidirectional"))
    )
    (net (code "59") (name "LCD_GMODE") (class "Default")
      (node (ref "IC1") (pin "40") (pinfunction "IOB_41_40") (pintype "bidirectional"))
      (node (ref "J1") (pin "28") (pinfunction "P$28_28") (pintype "bidirectional"))
      (node (ref "J1") (pin "29") (pinfunction "P$29_29") (pintype "bidirectional"))
    )
    (net (code "60") (name "LCD_GVDD") (class "Default")
      (node (ref "C25") (pin "1") (pinfunction "1_1") (pintype "passive"))
      (node (ref "D11") (pin "C") (pinfunction "C_C") (pintype "bidirectional"))
      (node (ref "J1") (pin "24") (pinfunction "P$24_24") (pintype "bidirectional"))
      (node (ref "R13") (pin "1") (pinfunction "1_1") (pintype "passive"))
      (node (ref "R15") (pin "2") (pinfunction "2_2") (pintype "passive"))
    )
    (net (code "61") (name "LCD_GVEE") (class "Default")
      (node (ref "C29") (pin "1") (pinfunction "1_1") (pintype "passive"))
      (node (ref "D13") (pin "A") (pinfunction "A_A") (pintype "bidirectional"))
      (node (ref "J1") (pin "26") (pinfunction "P$26_26") (pintype "bidirectional"))
      (node (ref "R11") (pin "2") (pinfunction "2_2") (pintype "passive"))
      (node (ref "R20") (pin "2") (pinfunction "2_2") (pintype "passive"))
    )
    (net (code "62") (name "LCD_LE") (class "Default")
      (node (ref "IC1") (pin "24") (pinfunction "IOL_12A_24") (pintype "bidirectional"))
      (node (ref "J1") (pin "9") (pinfunction "P$9_9") (pintype "bidirectional"))
    )
    (net (code "63") (name "LCD_OE") (class "Default")
      (node (ref "IC1") (pin "25") (pinfunction "IOL_12B_25") (pintype "bidirectional"))
      (node (ref "J1") (pin "10") (pinfunction "P$10_10") (pintype "bidirectional"))
    )
    (net (code "64") (name "LCD_SPH") (class "Default")
      (node (ref "IC1") (pin "26") (pinfunction "IOB_26_26") (pintype "bidirectional"))
      (node (ref "J1") (pin "12") (pinfunction "P$12_12") (pintype "bidirectional"))
    )
    (net (code "65") (name "LCD_SPV") (class "Default")
      (node (ref "IC1") (pin "41") (pinfunction "IOB_42_CBSEL0_41") (pintype "bidirectional"))
      (node (ref "J1") (pin "31") (pinfunction "P$31_31") (pintype "bidirectional"))
    )
    (net (code "66") (name "LCD_VCOM") (class "Default")
      (node (ref "C47") (pin "1") (pinfunction "1_1") (pintype "passive"))
      (node (ref "IC4") (pin "P15") (pinfunction "VCOM_P15") (pintype "bidirectional"))
      (node (ref "J1") (pin "22") (pinfunction "P$22_22") (pintype "bidirectional"))
      (node (ref "R17") (pin "2") (pinfunction "2_2") (pintype "passive"))
    )
    (net (code "67") (name "LCD_VNEG") (class "Default")
      (node (ref "C43") (pin "1") (pinfunction "1_1") (pintype "passive"))
      (node (ref "IC4") (pin "P$3") (pinfunction "VNEG_P$3") (pintype "bidirectional"))
      (node (ref "J1") (pin "1") (pinfunction "P$1_1") (pintype "bidirectional"))
      (node (ref "R16") (pin "2") (pinfunction "2_2") (pintype "passive"))
    )
    (net (code "68") (name "LCD_VPOS") (class "Default")
      (node (ref "C28") (pin "1") (pinfunction "1_1") (pintype "passive"))
      (node (ref "C48") (pin "2") (pinfunction "2_2") (pintype "passive"))
      (node (ref "IC4") (pin "P44") (pinfunction "VPOS_P44") (pintype "bidirectional"))
      (node (ref "J1") (pin "3") (pinfunction "P$3_3") (pintype "bidirectional"))
      (node (ref "R18") (pin "2") (pinfunction "2_2") (pintype "passive"))
    )
    (net (code "69") (name "Net-(C45-Pad2)") (class "Default")
      (node (ref "C45") (pin "2") (pinfunction "2_2") (pintype "passive"))
      (node (ref "D12") (pin "A") (pinfunction "A_A") (pintype "bidirectional"))
      (node (ref "D13") (pin "C") (pinfunction "C_C") (pintype "bidirectional"))
    )
    (net (code "70") (name "Net-(C46-Pad1)") (class "Default")
      (node (ref "C46") (pin "1") (pinfunction "1_1") (pintype "passive"))
      (node (ref "D10") (pin "C") (pinfunction "C_C") (pintype "bidirectional"))
      (node (ref "D11") (pin "A") (pinfunction "A_A") (pintype "bidirectional"))
    )
    (net (code "71") (name "Net-(IC3-CE#)") (class "Default")
      (node (ref "IC3") (pin "1") (pinfunction "CE#_1") (pintype "bidirectional"))
      (node (ref "R2") (pin "2") (pinfunction "2_2") (pintype "passive"))
      (node (ref "R3") (pin "1") (pinfunction "1_1") (pintype "passive"))
    )
    (net (code "72") (name "Net-(IC3-HOLD#)") (class "Default")
      (node (ref "IC3") (pin "3") (pinfunction "WP#_3") (pintype "bidirectional"))
      (node (ref "IC3") (pin "7") (pinfunction "HOLD#_7") (pintype "bidirectional"))
      (node (ref "R1") (pin "1") (pinfunction "1_1") (pintype "passive"))
    )
    (net (code "73") (name "Net-(IC4-INT_LDO)") (class "Default")
      (node (ref "C39") (pin "1") (pinfunction "1_1") (pintype "passive"))
      (node (ref "IC4") (pin "P$7") (pinfunction "INT_LDO_P$7") (pintype "bidirectional"))
    )
    (net (code "74") (name "Net-(IC4-TS)") (class "Default")
      (node (ref "IC4") (pin "P47") (pinfunction "TS_P47") (pintype "bidirectional"))
      (node (ref "NTC1") (pin "2") (pinfunction "2_2") (pintype "passive"))
      (node (ref "R19") (pin "2") (pinfunction "2_2") (pintype "passive"))
    )
    (net (code "75") (name "Net-(IC4-VB_SW)") (class "Default")
      (node (ref "D8") (pin "A") (pinfunction "A_A") (pintype "bidirectional"))
      (node (ref "IC4") (pin "P40") (pinfunction "VB_SW_P40") (pintype "bidirectional"))
      (node (ref "L3") (pin "P$2") (pinfunction "P$2_P$2") (pintype "bidirectional"))
    )
    (net (code "76") (name "Net-(IC4-VCOM_DIS)") (class "Default")
      (node (ref "IC4") (pin "P14") (pinfunction "VCOM_DIS_P14") (pintype "bidirectional"))
      (node (ref "R17") (pin "1") (pinfunction "1_1") (pintype "passive"))
    )
    (net (code "77") (name "Net-(IC4-VDDH_D)") (class "Default")
      (node (ref "C49") (pin "2") (pinfunction "2_2") (pintype "passive"))
      (node (ref "D10") (pin "A") (pinfunction "A_A") (pintype "bidirectional"))
      (node (ref "IC4") (pin "P34") (pinfunction "VDDH_D_P34") (pintype "bidirectional"))
    )
    (net (code "78") (name "Net-(IC4-VDDH_DIS)") (class "Default")
      (node (ref "IC4") (pin "P35") (pinfunction "VDDH_DIS_P35") (pintype "bidirectional"))
      (node (ref "R15") (pin "1") (pinfunction "1_1") (pintype "passive"))
    )
    (net (code "79") (name "Net-(IC4-VDDH_DRV)") (class "Default")
      (node (ref "C46") (pin "2") (pinfunction "2_2") (pintype "passive"))
      (node (ref "IC4") (pin "P36") (pinfunction "VDDH_DRV_P36") (pintype "bidirectional"))
    )
    (net (code "80") (name "Net-(IC4-VDDH_FB)") (class "Default")
      (node (ref "IC4") (pin "P33") (pinfunction "VDDH_FB_P33") (pintype "bidirectional"))
      (node (ref "R13") (pin "2") (pinfunction "2_2") (pintype "passive"))
      (node (ref "R14") (pin "1") (pinfunction "1_1") (pintype "passive"))
    )
    (net (code "81") (name "Net-(IC4-VEE_D)") (class "Default")
      (node (ref "C50") (pin "1") (pinfunction "1_1") (pintype "passive"))
      (node (ref "D12") (pin "C") (pinfunction "C_C") (pintype "bidirectional"))
      (node (ref "IC4") (pin "P30") (pinfunction "VEE_D_P30") (pintype "bidirectional"))
    )
    (net (code "82") (name "Net-(IC4-VEE_DIS)") (class "Default")
      (node (ref "IC4") (pin "P29") (pinfunction "VEE_DIS_P29") (pintype "bidirectional"))
      (node (ref "R20") (pin "1") (pinfunction "1_1") (pintype "passive"))
    )
    (net (code "83") (name "Net-(IC4-VEE_DRV)") (class "Default")
      (node (ref "C45") (pin "1") (pinfunction "1_1") (pintype "passive"))
      (node (ref "IC4") (pin "P28") (pinfunction "VEE_DRV_P28") (pintype "bidirectional"))
    )
    (net (code "84") (name "Net-(IC4-VEE_FB)") (class "Default")
      (node (ref "IC4") (pin "P31") (pinfunction "VEE_FB_P31") (pintype "bidirectional"))
      (node (ref "R11") (pin "1") (pinfunction "1_1") (pintype "passive"))
      (node (ref "R12") (pin "2") (pinfunction "2_2") (pintype "passive"))
    )
    (net (code "85") (name "Net-(IC4-VNEG_DIS)") (class "Default")
      (node (ref "IC4") (pin "P$9") (pinfunction "VNEG_DIS_P$9") (pintype "bidirectional"))
      (node (ref "R16") (pin "1") (pinfunction "1_1") (pintype "passive"))
    )
    (net (code "86") (name "Net-(IC4-VN_SW)") (class "Default")
      (node (ref "D9") (pin "C") (pinfunction "C_C") (pintype "bidirectional"))
      (node (ref "IC4") (pin "P25") (pinfunction "VN_SW_P25") (pintype "bidirectional"))
      (node (ref "L4") (pin "P$1") (pinfunction "P$1_P$1") (pintype "bidirectional"))
    )
    (net (code "87") (name "Net-(IC4-VPOS_DIS)") (class "Default")
      (node (ref "IC4") (pin "P19") (pinfunction "VPOS_DIS_P19") (pintype "bidirectional"))
      (node (ref "R18") (pin "1") (pinfunction "1_1") (pintype "passive"))
    )
    (net (code "88") (name "Net-(IC4-VREF)") (class "Default")
      (node (ref "C44") (pin "1") (pinfunction "1_1") (pintype "passive"))
      (node (ref "IC4") (pin "P$1") (pinfunction "VREF_P$1") (pintype "bidirectional"))
    )
    (net (code "89") (name "Net-(IC5-FB)") (class "Default")
      (node (ref "C17") (pin "1") (pinfunction "1_1") (pintype "passive"))
      (node (ref "IC5") (pin "5") (pinfunction "FB_5") (pintype "bidirectional"))
      (node (ref "R8") (pin "2") (pinfunction "2_2") (pintype "passive"))
      (node (ref "R9") (pin "2") (pinfunction "2_2") (pintype "passive"))
    )
    (net (code "90") (name "Net-(IC5-SW)") (class "Default")
      (node (ref "IC5") (pin "3") (pinfunction "SW_3") (pintype "bidirectional"))
      (node (ref "L1") (pin "P$1") (pinfunction "P$1_P$1") (pintype "bidirectional"))
    )
    (net (code "91") (name "Net-(IC6-FB)") (class "Default")
      (node (ref "C23") (pin "1") (pinfunction "1_1") (pintype "passive"))
      (node (ref "IC6") (pin "5") (pinfunction "FB_5") (pintype "bidirectional"))
      (node (ref "R10") (pin "2") (pinfunction "2_2") (pintype "passive"))
      (node (ref "R21") (pin "2") (pinfunction "2_2") (pintype "passive"))
    )
    (net (code "92") (name "Net-(IC6-SW)") (class "Default")
      (node (ref "IC6") (pin "3") (pinfunction "SW_3") (pintype "bidirectional"))
      (node (ref "L2") (pin "P$1") (pinfunction "P$1_P$1") (pintype "bidirectional"))
    )
    (net (code "93") (name "Net-(LED1-PadC)") (class "Default")
      (node (ref "LED1") (pin "C") (pinfunction "C_C") (pintype "passive"))
      (node (ref "R7") (pin "2") (pinfunction "2_2") (pintype "passive"))
    )
    (net (code "94") (name "Net-(LED2-PadA)") (class "Default")
      (node (ref "LED2") (pin "A") (pinfunction "A_A") (pintype "passive"))
      (node (ref "R22") (pin "2") (pinfunction "2_2") (pintype "passive"))
    )
    (net (code "95") (name "PG_PIN") (class "Default")
      (node (ref "IC4") (pin "P23") (pinfunction "PWR_GOOD_P23") (pintype "bidirectional"))
      (node (ref "LED2") (pin "C") (pinfunction "C_C") (pintype "passive"))
    )
    (net (code "96") (name "SCL_PIN") (class "Default")
      (node (ref "IC4") (pin "P17") (pinfunction "SCL_P17") (pintype "bidirectional"))
      (node (ref "J2") (pin "11") (pinfunction "11_11") (pintype "passive"))
    )
    (net (code "97") (name "SDA_PIN") (class "Default")
      (node (ref "IC4") (pin "P18") (pinfunction "SDA_P18") (pintype "bidirectional"))
      (node (ref "J2") (pin "12") (pinfunction "12_12") (pintype "passive"))
    )
    (net (code "98") (name "SPI_CLK") (class "Default")
      (node (ref "IC1") (pin "1") (pinfunction "IOL_1A_1") (pintype "bidirectional"))
      (node (ref "J2") (pin "1") (pinfunction "1_1") (pintype "passive"))
    )
    (net (code "99") (name "SPI_CMD") (class "Default")
      (node (ref "IC1") (pin "8") (pinfunction "IOL_3B_8") (pintype "bidirectional"))
      (node (ref "J2") (pin "7") (pinfunction "7_7") (pintype "passive"))
    )
    (net (code "100") (name "SPI_CS") (class "Default")
      (node (ref "IC1") (pin "9") (pinfunction "IOL_5A_9") (pintype "bidirectional"))
      (node (ref "J2") (pin "6") (pinfunction "6_6") (pintype "passive"))
    )
    (net (code "101") (name "SPI_DATA0") (class "Default")
      (node (ref "IC1") (pin "2") (pinfunction "IOL_1B_2") (pintype "bidirectional"))
      (node (ref "J2") (pin "2") (pinfunction "2_2") (pintype "passive"))
    )
    (net (code "102") (name "SPI_DATA1") (class "Default")
      (node (ref "IC1") (pin "3") (pinfunction "IOL_2A_3") (pintype "bidirectional"))
      (node (ref "J2") (pin "3") (pinfunction "3_3") (pintype "passive"))
    )
    (net (code "103") (name "SPI_DATA2") (class "Default")
      (node (ref "IC1") (pin "4") (pinfunction "IOL_2B_4") (pintype "bidirectional"))
      (node (ref "J2") (pin "4") (pinfunction "4_4") (pintype "passive"))
    )
    (net (code "104") (name "SPI_DATA3") (class "Default")
      (node (ref "IC1") (pin "7") (pinfunction "IOL_3A_7") (pintype "bidirectional"))
      (node (ref "J2") (pin "5") (pinfunction "5_5") (pintype "passive"))
    )
    (net (code "105") (name "VB") (class "Default")
      (node (ref "C35") (pin "1") (pinfunction "1_1") (pintype "passive"))
      (node (ref "C36") (pin "1") (pinfunction "1_1") (pintype "passive"))
      (node (ref "D8") (pin "C") (pinfunction "C_C") (pintype "bidirectional"))
      (node (ref "IC4") (pin "P37") (pinfunction "VDDH_IN_P37") (pintype "bidirectional"))
      (node (ref "IC4") (pin "P42") (pinfunction "VB_P42") (pintype "bidirectional"))
      (node (ref "IC4") (pin "P43") (pinfunction "VPOS_IN_P43") (pintype "bidirectional"))
    )
    (net (code "106") (name "VIN") (class "Default")
      (node (ref "C21") (pin "1") (pinfunction "1_1") (pintype "passive"))
      (node (ref "C24") (pin "1") (pinfunction "1_1") (pintype "passive"))
      (node (ref "IC5") (pin "1") (pinfunction "EN_1") (pintype "bidirectional"))
      (node (ref "IC5") (pin "4") (pinfunction "VIN_4") (pintype "bidirectional"))
      (node (ref "IC6") (pin "1") (pinfunction "EN_1") (pintype "bidirectional"))
      (node (ref "IC6") (pin "4") (pinfunction "VIN_4") (pintype "bidirectional"))
      (node (ref "J2") (pin "14") (pinfunction "14_14") (pintype "passive"))
    )
    (net (code "107") (name "VN") (class "Default")
      (node (ref "C37") (pin "1") (pinfunction "1_1") (pintype "passive"))
      (node (ref "C41") (pin "1") (pinfunction "1_1") (pintype "passive"))
      (node (ref "C42") (pin "1") (pinfunction "1_1") (pintype "passive"))
      (node (ref "D9") (pin "A") (pinfunction "A_A") (pintype "bidirectional"))
      (node (ref "IC4") (pin "GN0") (pinfunction "POWER_PAD_GN0") (pintype "bidirectional"))
      (node (ref "IC4") (pin "GN1") (pinfunction "POWER_PAD_GN1") (pintype "bidirectional"))
      (node (ref "IC4") (pin "GN10") (pinfunction "POWER_PAD_GN10") (pintype "bidirectional"))
      (node (ref "IC4") (pin "GN11") (pinfunction "POWER_PAD_GN11") (pintype "bidirectional"))
      (node (ref "IC4") (pin "GN12") (pinfunction "POWER_PAD_GN12") (pintype "bidirectional"))
      (node (ref "IC4") (pin "GN13") (pinfunction "POWER_PAD_GN13") (pintype "bidirectional"))
      (node (ref "IC4") (pin "GN14") (pinfunction "POWER_PAD_GN14") (pintype "bidirectional"))
      (node (ref "IC4") (pin "GN15") (pinfunction "POWER_PAD_GN15") (pintype "bidirectional"))
      (node (ref "IC4") (pin "GN16") (pinfunction "POWER_PAD_GN16") (pintype "bidirectional"))
      (node (ref "IC4") (pin "GN2") (pinfunction "POWER_PAD_GN2") (pintype "bidirectional"))
      (node (ref "IC4") (pin "GN3") (pinfunction "POWER_PAD_GN3") (pintype "bidirectional"))
      (node (ref "IC4") (pin "GN4") (pinfunction "POWER_PAD_GN4") (pintype "bidirectional"))
      (node (ref "IC4") (pin "GN5") (pinfunction "POWER_PAD_GN5") (pintype "bidirectional"))
      (node (ref "IC4") (pin "GN6") (pinfunction "POWER_PAD_GN6") (pintype "bidirectional"))
      (node (ref "IC4") (pin "GN7") (pinfunction "POWER_PAD_GN7") (pintype "bidirectional"))
      (node (ref "IC4") (pin "GN8") (pinfunction "POWER_PAD_GN8") (pintype "bidirectional"))
      (node (ref "IC4") (pin "GN9") (pinfunction "POWER_PAD_GN9") (pintype "bidirectional"))
      (node (ref "IC4") (pin "P$4") (pinfunction "VNEG_IN_P$4") (pintype "bidirectional"))
      (node (ref "IC4") (pin "P16") (pinfunction "VCOM_PWR_P16") (pintype "bidirectional"))
      (node (ref "IC4") (pin "P22") (pinfunction "PBKG_P22") (pintype "bidirectional"))
      (node (ref "IC4") (pin "P26") (pinfunction "VN_P26") (pintype "bidirectional"))
      (node (ref "IC4") (pin "P27") (pinfunction "VEE_IN_P27") (pintype "bidirectional"))
    )
    (net (code "108") (name "WAKE_PIN") (class "Default")
      (node (ref "IC4") (pin "P$5") (pinfunction "WAKEUP_P$5") (pintype "bidirectional"))
      (node (ref "J2") (pin "9") (pinfunction "9_9") (pintype "passive"))
    )
    (net (code "109") (name "unconnected-(IC1-IOL_5B-Pad10)") (class "Default")
      (node (ref "IC1") (pin "10") (pinfunction "IOL_5B_10") (pintype "bidirectional"))
    )
    (net (code "110") (name "unconnected-(IC1-IOL_6A-Pad12)") (class "Default")
      (node (ref "IC1") (pin "12") (pinfunction "IOL_6A_12") (pintype "bidirectional"))
    )
    (net (code "111") (name "unconnected-(IC1-IOL_6B_GBIN7-Pad13)") (class "Default")
      (node (ref "IC1") (pin "13") (pinfunction "IOL_6B_GBIN7_13") (pintype "bidirectional"))
    )
    (net (code "112") (name "unconnected-(IC1-IOL_7B-Pad16)") (class "Default")
      (node (ref "IC1") (pin "16") (pinfunction "IOL_7B_16") (pintype "bidirectional"))
    )
    (net (code "113") (name "unconnected-(IC1-IOL_8A-Pad18)") (class "Default")
      (node (ref "IC1") (pin "18") (pinfunction "IOL_8A_18") (pintype "bidirectional"))
    )
    (net (code "114") (name "unconnected-(IC1-IOL_8B-Pad19)") (class "Default")
      (node (ref "IC1") (pin "19") (pinfunction "IOL_8B_19") (pintype "bidirectional"))
    )
    (net (code "115") (name "unconnected-(IC1-IOL_10A-Pad20)") (class "Default")
      (node (ref "IC1") (pin "20") (pinfunction "IOL_10A_20") (pintype "bidirectional"))
    )
    (net (code "116") (name "unconnected-(IC1-VPP_FAST-Pad76)") (class "Default")
      (node (ref "IC1") (pin "76") (pinfunction "VPP_FAST_76") (pintype "bidirectional"))
    )
    (net (code "117") (name "unconnected-(IC4-V3P3-PadP46)") (class "Default")
      (node (ref "IC4") (pin "P46") (pinfunction "V3P3_P46") (pintype "bidirectional"))
    )
    (net (code "118") (name "unconnected-(J1-P$2-Pad2)") (class "Default")
      (node (ref "J1") (pin "2") (pinfunction "P$2_2") (pintype "bidirectional"))
    )
    (net (code "119") (name "unconnected-(J1-P$4-Pad4)") (class "Default")
      (node (ref "J1") (pin "4") (pinfunction "P$4_4") (pintype "bidirectional"))
    )
    (net (code "120") (name "unconnected-(J1-P$6-Pad6)") (class "Default")
      (node (ref "J1") (pin "6") (pinfunction "P$6_6") (pintype "bidirectional"))
    )
    (net (code "121") (name "unconnected-(J1-P$21-Pad21)") (class "Default")
      (node (ref "J1") (pin "21") (pinfunction "P$21_21") (pintype "bidirectional"))
    )
    (net (code "122") (name "unconnected-(J1-P$23-Pad23)") (class "Default")
      (node (ref "J1") (pin "23") (pinfunction "P$23_23") (pintype "bidirectional"))
    )
    (net (code "123") (name "unconnected-(J1-P$25-Pad25)") (class "Default")
      (node (ref "J1") (pin "25") (pinfunction "P$25_25") (pintype "bidirectional"))
    )
    (net (code "124") (name "unconnected-(J1-P$27-Pad27)") (class "Default")
      (node (ref "J1") (pin "27") (pinfunction "P$27_27") (pintype "bidirectional"))
    )
    (net (code "125") (name "unconnected-(X1-Pad1)") (class "Default")
      (node (ref "X1") (pin "1") (pinfunction "1_1") (pintype "bidirectional"))
    )
    (net (code "126") (name "~{CE}") (class "Default")
      (node (ref "IC1") (pin "54") (pinfunction "IOR_55_54") (pintype "bidirectional"))
      (node (ref "IC2") (pin "6") (pinfunction "~{CE}_6") (pintype "bidirectional"))
      (node (ref "R4") (pin "2") (pinfunction "2_2") (pintype "passive"))
    )
    (net (code "127") (name "~{OE}") (class "Default")
      (node (ref "IC1") (pin "51") (pinfunction "IOR_52_51") (pintype "bidirectional"))
      (node (ref "IC2") (pin "41") (pinfunction "~{OE}_41") (pintype "bidirectional"))
    )
    (net (code "128") (name "~{WE}") (class "Default")
      (node (ref "IC1") (pin "74") (pinfunction "IOR_72_74") (pintype "bidirectional"))
      (node (ref "IC2") (pin "17") (pinfunction "~{WE}_17") (pintype "bidirectional"))
    )
  )
)
